# GyroAccelHeaders.net
KiCad netlist of a schematic drawn in Altium Designer
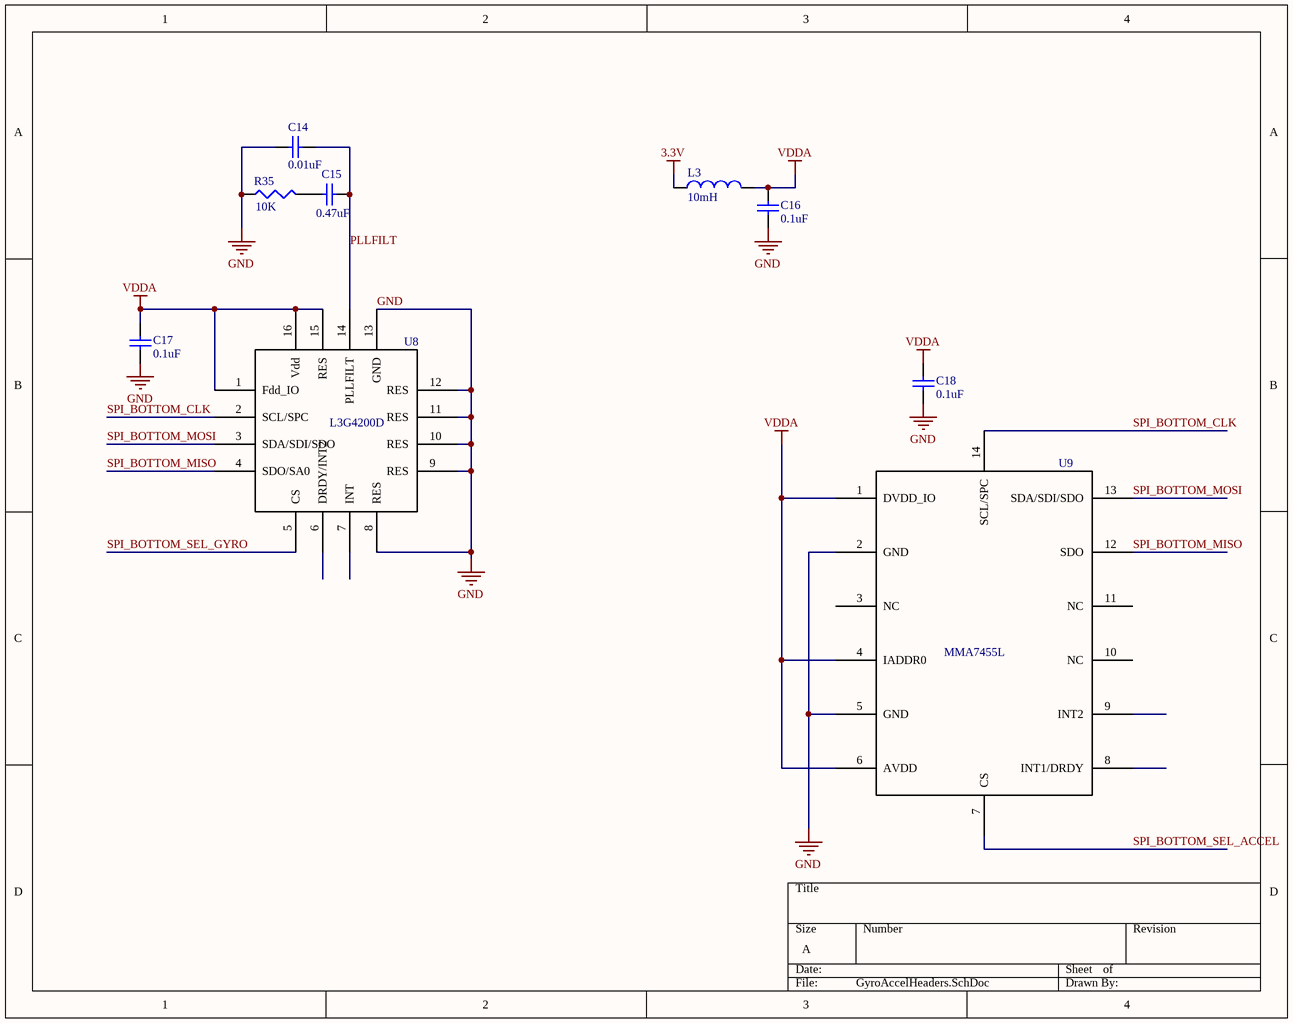
[diagram p0: GyroAccelHeaders.SchDoc]

(export (version "E")
  (design (tool "Eeschema 10.0.6"))
  (components
    (comp (ref "C14")
      (value "0.01uF")
      (footprint "CAPC1005L")
      (description "Capacitor (Semiconductor SIM Model)")
      (fields (field (name "Comment") "Cap Semi") (field (name "PUBLISHER") "Altium Limited"))
      (libsource (lib "Miscellaneous Devices") (part "Cap Semi"))
    )
    (comp (ref "C15")
      (value "0.47uF")
      (footprint "CAPC1005L")
      (description "Capacitor (Semiconductor SIM Model)")
      (fields (field (name "Comment") "Cap Semi") (field (name "PUBLISHER") "Altium Limited"))
      (libsource (lib "Miscellaneous Devices") (part "Cap Semi"))
    )
    (comp (ref "C16")
      (value "0.1uF")
      (footprint "CAPC1005L")
      (description "Capacitor (Semiconductor SIM Model)")
      (fields (field (name "Comment") "Cap Semi") (field (name "PUBLISHER") "Altium Limited"))
      (libsource (lib "Miscellaneous Devices") (part "Cap Semi"))
    )
    (comp (ref "C17")
      (value "0.1uF")
      (footprint "CAPC1005L")
      (description "Capacitor (Semiconductor SIM Model)")
      (fields (field (name "Comment") "Cap Semi") (field (name "PUBLISHER") "Altium Limited"))
      (libsource (lib "Miscellaneous Devices") (part "Cap Semi"))
    )
    (comp (ref "C18")
      (value "0.1uF")
      (footprint "CAPC1005L")
      (description "Capacitor (Semiconductor SIM Model)")
      (fields (field (name "Comment") "Cap Semi") (field (name "PUBLISHER") "Altium Limited"))
      (libsource (lib "Miscellaneous Devices") (part "Cap Semi"))
    )
    (comp (ref "L3")
      (value "10mH")
      (footprint "INDC2012L")
      (description "Inductor")
      (fields (field (name "PUBLISHER") "Altium Limited"))
      (libsource (lib "Miscellaneous Devices") (part "Inductor"))
    )
    (comp (ref "R35")
      (value "10K")
      (footprint "RESC1608L")
      (description "Resistor")
      (fields (field (name "Comment") "Res3") (field (name "PUBLISHER") "Altium Limited"))
      (libsource (lib "Miscellaneous Devices") (part "Res3"))
    )
    (comp (ref "U8")
      (value "L3G4200D")
      (footprint "L3G2004D")
      (description "3axis gyroscope, SPI")
      (libsource (lib "mrone") (part "L3G4200D"))
    )
    (comp (ref "U9")
      (value "MMA7455L")
      (footprint "MMA7455L")
      (description "3axis accelerometer")
      (libsource (lib "mrone") (part "MMA7455L"))
    )
  )
  (nets
    (net (code "1") (name "/PLLFILT") (class "Default")
      (node (ref "C14") (pin "1") (pinfunction "1_1") (pintype "passive"))
      (node (ref "C15") (pin "1") (pinfunction "1_1") (pintype "passive"))
      (node (ref "U8") (pin "14") (pinfunction "PLLFILT_14") (pintype "passive"))
    )
    (net (code "2") (name "/SPI_BOTTOM_CLK") (class "Default")
      (node (ref "U8") (pin "2") (pinfunction "SCL/SPC_2") (pintype "passive"))
      (node (ref "U9") (pin "14") (pinfunction "SCL/SPC_14") (pintype "passive"))
    )
    (net (code "3") (name "/SPI_BOTTOM_MISO") (class "Default")
      (node (ref "U8") (pin "4") (pinfunction "SDO/SA0_4") (pintype "passive"))
      (node (ref "U9") (pin "12") (pinfunction "SDO_12") (pintype "passive"))
    )
    (net (code "4") (name "/SPI_BOTTOM_MOSI") (class "Default")
      (node (ref "U8") (pin "3") (pinfunction "SDA/SDI/SDO_3") (pintype "passive"))
      (node (ref "U9") (pin "13") (pinfunction "SDA/SDI/SDO_13") (pintype "passive"))
    )
    (net (code "5") (name "/SPI_BOTTOM_SEL_ACCEL") (class "Default")
      (node (ref "U9") (pin "7") (pinfunction "CS_7") (pintype "passive"))
    )
    (net (code "6") (name "/SPI_BOTTOM_SEL_GYRO") (class "Default")
      (node (ref "U8") (pin "5") (pinfunction "CS_5") (pintype "passive"))
    )
    (net (code "7") (name "3.3V") (class "Default")
      (node (ref "L3") (pin "2") (pinfunction "2_2") (pintype "passive"))
    )
    (net (code "8") (name "GND") (class "Default")
      (node (ref "C14") (pin "2") (pinfunction "2_2") (pintype "passive"))
      (node (ref "C16") (pin "1") (pinfunction "1_1") (pintype "passive"))
      (node (ref "C17") (pin "1") (pinfunction "1_1") (pintype "passive"))
      (node (ref "C18") (pin "1") (pinfunction "1_1") (pintype "passive"))
      (node (ref "R35") (pin "1") (pinfunction "1_1") (pintype "passive"))
      (node (ref "U8") (pin "10") (pinfunction "RES_10") (pintype "passive"))
      (node (ref "U8") (pin "11") (pinfunction "RES_11") (pintype "passive"))
      (node (ref "U8") (pin "12") (pinfunction "RES_12") (pintype "passive"))
      (node (ref "U8") (pin "13") (pinfunction "GND_13") (pintype "passive"))
      (node (ref "U8") (pin "8") (pinfunction "RES_8") (pintype "passive"))
      (node (ref "U8") (pin "9") (pinfunction "RES_9") (pintype "passive"))
      (node (ref "U9") (pin "2") (pinfunction "GND_2") (pintype "passive"))
      (node (ref "U9") (pin "5") (pinfunction "GND_5") (pintype "passive"))
    )
    (net (code "9") (name "Net-(C15-Pad2)") (class "Default")
      (node (ref "C15") (pin "2") (pinfunction "2_2") (pintype "passive"))
      (node (ref "R35") (pin "2") (pinfunction "2_2") (pintype "passive"))
    )
    (net (code "10") (name "VDDA") (class "Default")
      (node (ref "C16") (pin "2") (pinfunction "2_2") (pintype "passive"))
      (node (ref "C17") (pin "2") (pinfunction "2_2") (pintype "passive"))
      (node (ref "C18") (pin "2") (pinfunction "2_2") (pintype "passive"))
      (node (ref "L3") (pin "1") (pinfunction "1_1") (pintype "passive"))
      (node (ref "U8") (pin "1") (pinfunction "Fdd_IO_1") (pintype "passive"))
      (node (ref "U8") (pin "15") (pinfunction "RES_15") (pintype "passive"))
      (node (ref "U8") (pin "16") (pinfunction "Vdd_16") (pintype "passive"))
      (node (ref "U9") (pin "1") (pinfunction "DVDD_IO_1") (pintype "passive"))
      (node (ref "U9") (pin "4") (pinfunction "IADDR0_4") (pintype "passive"))
      (node (ref "U9") (pin "6") (pinfunction "AVDD_6") (pintype "passive"))
    )
    (net (code "11") (name "unconnected-(U8-DRDY{slash}INT2-Pad6)") (class "Default")
      (node (ref "U8") (pin "6") (pinfunction "DRDY/INT2_6") (pintype "passive"))
    )
    (net (code "12") (name "unconnected-(U8-INT-Pad7)") (class "Default")
      (node (ref "U8") (pin "7") (pinfunction "INT_7") (pintype "passive"))
    )
    (net (code "13") (name "unconnected-(U9-INT1{slash}DRDY-Pad8)") (class "Default")
      (node (ref "U9") (pin "8") (pinfunction "INT1/DRDY_8") (pintype "passive"))
    )
    (net (code "14") (name "unconnected-(U9-INT2-Pad9)") (class "Default")
      (node (ref "U9") (pin "9") (pinfunction "INT2_9") (pintype "passive"))
    )
    (net (code "15") (name "unconnected-(U9-NC-Pad3)") (class "Default")
      (node (ref "U9") (pin "3") (pinfunction "NC_3") (pintype "passive"))
    )
    (net (code "16") (name "unconnected-(U9-NC-Pad10)") (class "Default")
      (node (ref "U9") (pin "10") (pinfunction "NC_10") (pintype "passive"))
    )
    (net (code "17") (name "unconnected-(U9-NC-Pad11)") (class "Default")
      (node (ref "U9") (pin "11") (pinfunction "NC_11") (pintype "passive"))
    )
  )
)
